# receiver.net
KiCad netlist of a schematic drawn in EAGLE
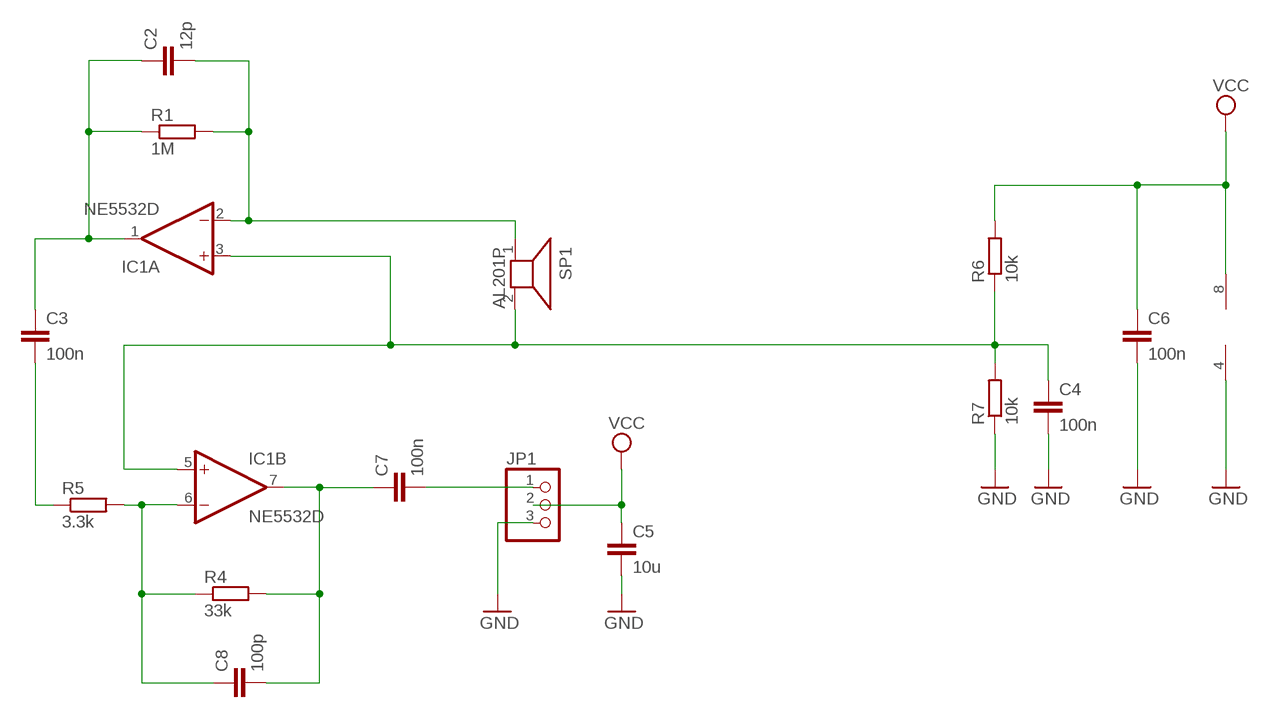
[diagram p0: schematic, sheet 1]

(export (version "E")
  (design (tool "Eeschema 10.0.6"))
  (components
    (comp (ref "C2")
      (value "12p")
      (footprint "eagle-import:C0805")
      (libsource (lib "eagle-import") (part "C-EUC0805"))
    )
    (comp (ref "C3")
      (value "100n")
      (footprint "eagle-import:C0805")
      (libsource (lib "eagle-import") (part "C-EUC0805"))
    )
    (comp (ref "C4")
      (value "100n")
      (footprint "eagle-import:C0805")
      (libsource (lib "eagle-import") (part "C-EUC0805"))
    )
    (comp (ref "C5")
      (value "10u")
      (footprint "eagle-import:C0805")
      (libsource (lib "eagle-import") (part "C-EUC0805"))
    )
    (comp (ref "C6")
      (value "100n")
      (footprint "eagle-import:C1206")
      (libsource (lib "eagle-import") (part "C-EUC1206"))
    )
    (comp (ref "C7")
      (value "100n")
      (footprint "eagle-import:C1206K")
      (libsource (lib "eagle-import") (part "C-EUC1206K"))
    )
    (comp (ref "C8")
      (value "100p")
      (footprint "eagle-import:C0805")
      (libsource (lib "eagle-import") (part "C-EUC0805"))
    )
    (comp (ref "IC1")
      (value "NE5532D")
      (footprint "eagle-import:SO08")
      (libsource (lib "eagle-import") (part "NE5532D"))
    )
    (comp (ref "JP1")
      (value "PINHD-1X3")
      (footprint "eagle-import:1X03")
      (libsource (lib "eagle-import") (part "PINHD-1X3"))
    )
    (comp (ref "R1")
      (value "1M")
      (footprint "eagle-import:R0805")
      (libsource (lib "eagle-import") (part "R-EU_R0805"))
    )
    (comp (ref "R4")
      (value "33k")
      (footprint "eagle-import:R0805")
      (libsource (lib "eagle-import") (part "R-EU_R0805"))
    )
    (comp (ref "R5")
      (value "3.3k")
      (footprint "eagle-import:R0805")
      (libsource (lib "eagle-import") (part "R-EU_R0805"))
    )
    (comp (ref "R6")
      (value "10k")
      (footprint "eagle-import:R0805")
      (libsource (lib "eagle-import") (part "R-EU_R0805"))
    )
    (comp (ref "R7")
      (value "10k")
      (footprint "eagle-import:R0805")
      (libsource (lib "eagle-import") (part "R-EU_R0805"))
    )
    (comp (ref "SP1")
      (value "AL201P")
      (footprint "eagle-import:AL201P")
      (libsource (lib "eagle-import") (part "AL201P"))
    )
  )
  (nets
    (net (code "1") (name "GND") (class "Default")
      (node (ref "C4") (pin "2") (pinfunction "2_2") (pintype "passive"))
      (node (ref "C5") (pin "2") (pinfunction "2_2") (pintype "passive"))
      (node (ref "C6") (pin "2") (pinfunction "2_2") (pintype "passive"))
      (node (ref "IC1") (pin "4") (pinfunction "V-_4") (pintype "power_in"))
      (node (ref "JP1") (pin "3") (pinfunction "3_3") (pintype "passive"))
      (node (ref "R7") (pin "1") (pinfunction "1_1") (pintype "passive"))
    )
    (net (code "2") (name "Net-(C3-Pad2)") (class "Default")
      (node (ref "C3") (pin "2") (pinfunction "2_2") (pintype "passive"))
      (node (ref "R5") (pin "1") (pinfunction "1_1") (pintype "passive"))
    )
    (net (code "3") (name "Net-(C7-Pad2)") (class "Default")
      (node (ref "C7") (pin "2") (pinfunction "2_2") (pintype "passive"))
      (node (ref "JP1") (pin "1") (pinfunction "1_1") (pintype "passive"))
    )
    (net (code "4") (name "Net-(IC1A-+IN)") (class "Default")
      (node (ref "C4") (pin "1") (pinfunction "1_1") (pintype "passive"))
      (node (ref "IC1") (pin "3") (pinfunction "+IN_3") (pintype "input"))
      (node (ref "IC1") (pin "5") (pinfunction "+IN_5") (pintype "input"))
      (node (ref "R6") (pin "1") (pinfunction "1_1") (pintype "passive"))
      (node (ref "R7") (pin "2") (pinfunction "2_2") (pintype "passive"))
      (node (ref "SP1") (pin "2") (pinfunction "2_2") (pintype "passive"))
    )
    (net (code "5") (name "Net-(IC1A--IN)") (class "Default")
      (node (ref "C2") (pin "2") (pinfunction "2_2") (pintype "passive"))
      (node (ref "IC1") (pin "2") (pinfunction "-IN_2") (pintype "input"))
      (node (ref "R1") (pin "2") (pinfunction "2_2") (pintype "passive"))
      (node (ref "SP1") (pin "1") (pinfunction "1_1") (pintype "passive"))
    )
    (net (code "6") (name "Net-(IC1A-OUT)") (class "Default")
      (node (ref "C2") (pin "1") (pinfunction "1_1") (pintype "passive"))
      (node (ref "C3") (pin "1") (pinfunction "1_1") (pintype "passive"))
      (node (ref "IC1") (pin "1") (pinfunction "OUT_1") (pintype "output"))
      (node (ref "R1") (pin "1") (pinfunction "1_1") (pintype "passive"))
    )
    (net (code "7") (name "Net-(IC1B--IN)") (class "Default")
      (node (ref "C8") (pin "1") (pinfunction "1_1") (pintype "passive"))
      (node (ref "IC1") (pin "6") (pinfunction "-IN_6") (pintype "input"))
      (node (ref "R4") (pin "1") (pinfunction "1_1") (pintype "passive"))
      (node (ref "R5") (pin "2") (pinfunction "2_2") (pintype "passive"))
    )
    (net (code "8") (name "Net-(IC1B-OUT)") (class "Default")
      (node (ref "C7") (pin "1") (pinfunction "1_1") (pintype "passive"))
      (node (ref "C8") (pin "2") (pinfunction "2_2") (pintype "passive"))
      (node (ref "IC1") (pin "7") (pinfunction "OUT_7") (pintype "output"))
      (node (ref "R4") (pin "2") (pinfunction "2_2") (pintype "passive"))
    )
    (net (code "9") (name "VCC") (class "Default")
      (node (ref "C5") (pin "1") (pinfunction "1_1") (pintype "passive"))
      (node (ref "C6") (pin "1") (pinfunction "1_1") (pintype "passive"))
      (node (ref "IC1") (pin "8") (pinfunction "V+_8") (pintype "power_in"))
      (node (ref "JP1") (pin "2") (pinfunction "2_2") (pintype "passive"))
      (node (ref "R6") (pin "2") (pinfunction "2_2") (pintype "passive"))
    )
  )
)
